# 411_Final_version_3.net
KiCad netlist of a schematic drawn in EAGLE
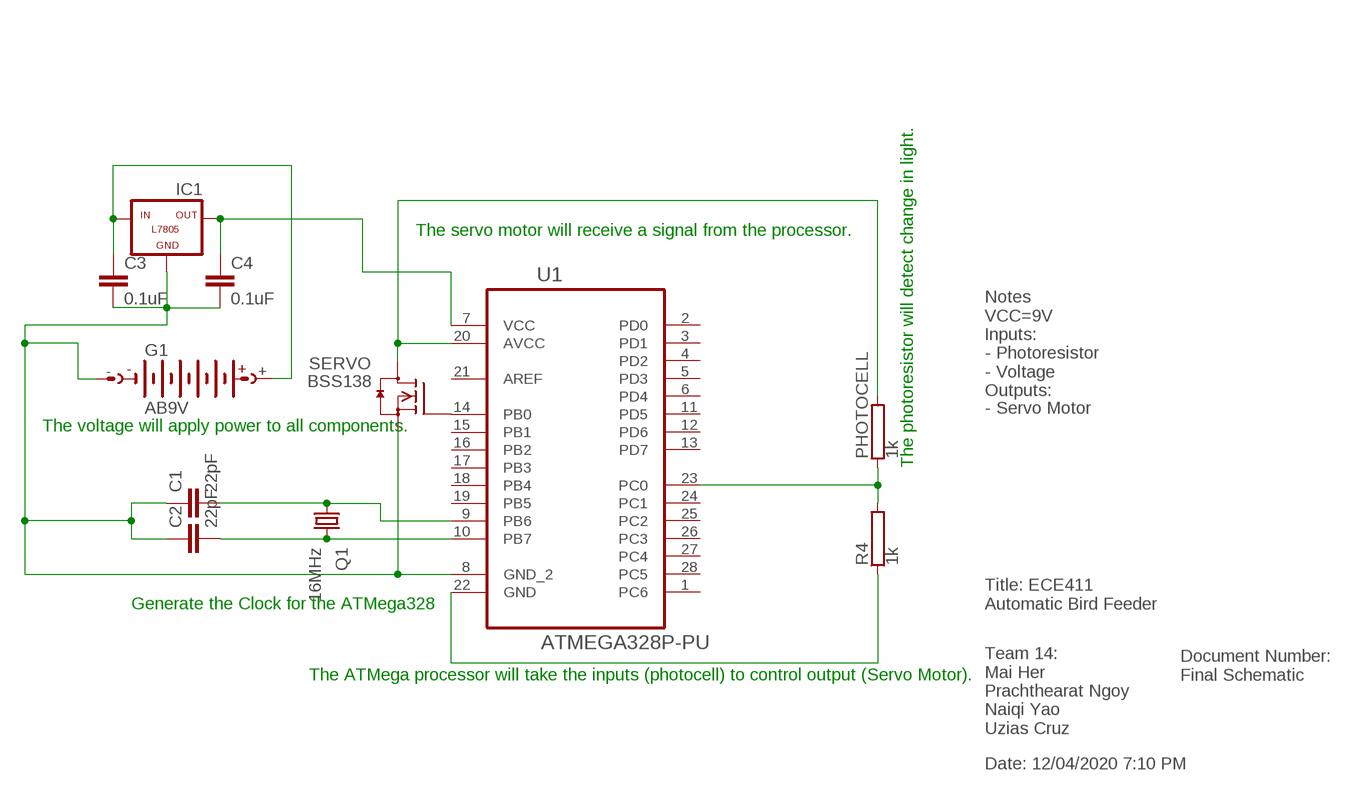
[diagram p0: schematic, sheet 1]

(export (version "E")
  (design (tool "Eeschema 10.0.6"))
  (components
    (comp (ref "C1")
      (value "22pF")
      (footprint "eagle-import:C2.5-3")
      (libsource (lib "eagle-import") (part "C2,5-3"))
    )
    (comp (ref "C2")
      (value "22pF")
      (footprint "eagle-import:C2.5-3")
      (libsource (lib "eagle-import") (part "C2,5-3"))
    )
    (comp (ref "C3")
      (value "0.1uF")
      (footprint "eagle-import:C2.5-3")
      (libsource (lib "eagle-import") (part "C2,5-3"))
    )
    (comp (ref "C4")
      (value "0.1uF")
      (footprint "eagle-import:C2.5-3")
      (libsource (lib "eagle-import") (part "C2,5-3"))
    )
    (comp (ref "G1")
      (value "AB9V")
      (footprint "eagle-import:AB9V")
      (libsource (lib "eagle-import") (part "AB9V"))
    )
    (comp (ref "IC1")
      (value "L7805")
      (footprint "eagle-import:78XXL")
      (libsource (lib "eagle-import") (part "L7805"))
    )
    (comp (ref "PHOTOCELL")
      (value "1k")
      (footprint "eagle-import:AC01")
      (libsource (lib "eagle-import") (part "RAC01"))
    )
    (comp (ref "Q1")
      (value "16MHz")
      (footprint "eagle-import:2.5X2.0_KX-6")
      (libsource (lib "eagle-import") (part "KX-6"))
    )
    (comp (ref "R4")
      (value "1k")
      (footprint "eagle-import:AC01")
      (libsource (lib "eagle-import") (part "RAC01"))
    )
    (comp (ref "SERVO")
      (value "BSS138")
      (footprint "eagle-import:SOT23")
      (libsource (lib "eagle-import") (part "BSS138"))
    )
    (comp (ref "U1")
      (value "ATMEGA328P-PU")
      (footprint "eagle-import:DIP254P762X457-28")
      (libsource (lib "eagle-import") (part "ATMEGA328P-PU"))
    )
  )
  (nets
    (net (code "1") (name "Net-(C3-Pad1)") (class "Default")
      (node (ref "C3") (pin "1") (pinfunction "1_1") (pintype "passive"))
      (node (ref "G1") (pin "+") (pinfunction "+_+") (pintype "passive"))
      (node (ref "IC1") (pin "IN") (pinfunction "IN_IN") (pintype "input"))
    )
    (net (code "2") (name "Net-(Q1-2)") (class "Default")
      (node (ref "C2") (pin "2") (pinfunction "2_2") (pintype "passive"))
      (node (ref "Q1") (pin "3") (pinfunction "2_3") (pintype "passive"))
      (node (ref "U1") (pin "10") (pinfunction "PB7_10") (pintype "bidirectional"))
    )
    (net (code "3") (name "Net-(SERVO-D)") (class "Default")
      (node (ref "PHOTOCELL") (pin "2") (pinfunction "2_2") (pintype "passive"))
      (node (ref "SERVO") (pin "3") (pinfunction "D_3") (pintype "passive"))
      (node (ref "U1") (pin "20") (pinfunction "AVCC_20") (pintype "power_in"))
    )
    (net (code "4") (name "Net-(SERVO-G)") (class "Default")
      (node (ref "SERVO") (pin "1") (pinfunction "G_1") (pintype "passive"))
      (node (ref "U1") (pin "14") (pinfunction "PB0_14") (pintype "bidirectional"))
    )
    (net (code "5") (name "Net-(SERVO-S)") (class "Default")
      (node (ref "C1") (pin "1") (pinfunction "1_1") (pintype "passive"))
      (node (ref "C2") (pin "1") (pinfunction "1_1") (pintype "passive"))
      (node (ref "C3") (pin "2") (pinfunction "2_2") (pintype "passive"))
      (node (ref "C4") (pin "2") (pinfunction "2_2") (pintype "passive"))
      (node (ref "G1") (pin "-") (pinfunction "-_-") (pintype "passive"))
      (node (ref "IC1") (pin "GND") (pinfunction "GND_GND") (pintype "input"))
      (node (ref "SERVO") (pin "2") (pinfunction "S_2") (pintype "passive"))
      (node (ref "U1") (pin "8") (pinfunction "GND_2_8") (pintype "passive"))
    )
    (net (code "6") (name "Net-(U1-GND)") (class "Default")
      (node (ref "R4") (pin "1") (pinfunction "1_1") (pintype "passive"))
      (node (ref "U1") (pin "22") (pinfunction "GND_22") (pintype "passive"))
    )
    (net (code "7") (name "Net-(U1-PB6)") (class "Default")
      (node (ref "C1") (pin "2") (pinfunction "2_2") (pintype "passive"))
      (node (ref "Q1") (pin "1") (pinfunction "1_1") (pintype "passive"))
      (node (ref "U1") (pin "9") (pinfunction "PB6_9") (pintype "bidirectional"))
    )
    (net (code "8") (name "Net-(U1-PC0)") (class "Default")
      (node (ref "PHOTOCELL") (pin "1") (pinfunction "1_1") (pintype "passive"))
      (node (ref "R4") (pin "2") (pinfunction "2_2") (pintype "passive"))
      (node (ref "U1") (pin "23") (pinfunction "PC0_23") (pintype "bidirectional"))
    )
    (net (code "9") (name "Net-(U1-VCC)") (class "Default")
      (node (ref "C4") (pin "1") (pinfunction "1_1") (pintype "passive"))
      (node (ref "IC1") (pin "OUT") (pinfunction "OUT_OUT") (pintype "passive"))
      (node (ref "U1") (pin "7") (pinfunction "VCC_7") (pintype "power_in"))
    )
    (net (code "10") (name "unconnected-(U1-AREF-Pad21)") (class "Default")
      (node (ref "U1") (pin "21") (pinfunction "AREF_21") (pintype "input"))
    )
    (net (code "11") (name "unconnected-(U1-PB1-Pad15)") (class "Default")
      (node (ref "U1") (pin "15") (pinfunction "PB1_15") (pintype "bidirectional"))
    )
    (net (code "12") (name "unconnected-(U1-PB2-Pad16)") (class "Default")
      (node (ref "U1") (pin "16") (pinfunction "PB2_16") (pintype "bidirectional"))
    )
    (net (code "13") (name "unconnected-(U1-PB3-Pad17)") (class "Default")
      (node (ref "U1") (pin "17") (pinfunction "PB3_17") (pintype "bidirectional"))
    )
    (net (code "14") (name "unconnected-(U1-PB4-Pad18)") (class "Default")
      (node (ref "U1") (pin "18") (pinfunction "PB4_18") (pintype "bidirectional"))
    )
    (net (code "15") (name "unconnected-(U1-PB5-Pad19)") (class "Default")
      (node (ref "U1") (pin "19") (pinfunction "PB5_19") (pintype "bidirectional"))
    )
    (net (code "16") (name "unconnected-(U1-PC1-Pad24)") (class "Default")
      (node (ref "U1") (pin "24") (pinfunction "PC1_24") (pintype "bidirectional"))
    )
    (net (code "17") (name "unconnected-(U1-PC2-Pad25)") (class "Default")
      (node (ref "U1") (pin "25") (pinfunction "PC2_25") (pintype "bidirectional"))
    )
    (net (code "18") (name "unconnected-(U1-PC3-Pad26)") (class "Default")
      (node (ref "U1") (pin "26") (pinfunction "PC3_26") (pintype "bidirectional"))
    )
    (net (code "19") (name "unconnected-(U1-PC4-Pad27)") (class "Default")
      (node (ref "U1") (pin "27") (pinfunction "PC4_27") (pintype "bidirectional"))
    )
    (net (code "20") (name "unconnected-(U1-PC5-Pad28)") (class "Default")
      (node (ref "U1") (pin "28") (pinfunction "PC5_28") (pintype "bidirectional"))
    )
    (net (code "21") (name "unconnected-(U1-PC6-Pad1)") (class "Default")
      (node (ref "U1") (pin "1") (pinfunction "PC6_1") (pintype "bidirectional"))
    )
    (net (code "22") (name "unconnected-(U1-PD0-Pad2)") (class "Default")
      (node (ref "U1") (pin "2") (pinfunction "PD0_2") (pintype "bidirectional"))
    )
    (net (code "23") (name "unconnected-(U1-PD1-Pad3)") (class "Default")
      (node (ref "U1") (pin "3") (pinfunction "PD1_3") (pintype "bidirectional"))
    )
    (net (code "24") (name "unconnected-(U1-PD2-Pad4)") (class "Default")
      (node (ref "U1") (pin "4") (pinfunction "PD2_4") (pintype "bidirectional"))
    )
    (net (code "25") (name "unconnected-(U1-PD3-Pad5)") (class "Default")
      (node (ref "U1") (pin "5") (pinfunction "PD3_5") (pintype "bidirectional"))
    )
    (net (code "26") (name "unconnected-(U1-PD4-Pad6)") (class "Default")
      (node (ref "U1") (pin "6") (pinfunction "PD4_6") (pintype "bidirectional"))
    )
    (net (code "27") (name "unconnected-(U1-PD5-Pad11)") (class "Default")
      (node (ref "U1") (pin "11") (pinfunction "PD5_11") (pintype "bidirectional"))
    )
    (net (code "28") (name "unconnected-(U1-PD6-Pad12)") (class "Default")
      (node (ref "U1") (pin "12") (pinfunction "PD6_12") (pintype "bidirectional"))
    )
    (net (code "29") (name "unconnected-(U1-PD7-Pad13)") (class "Default")
      (node (ref "U1") (pin "13") (pinfunction "PD7_13") (pintype "bidirectional"))
    )
  )
)
